# ai_breakout_apa102.net
KiCad netlist of a schematic drawn in EAGLE
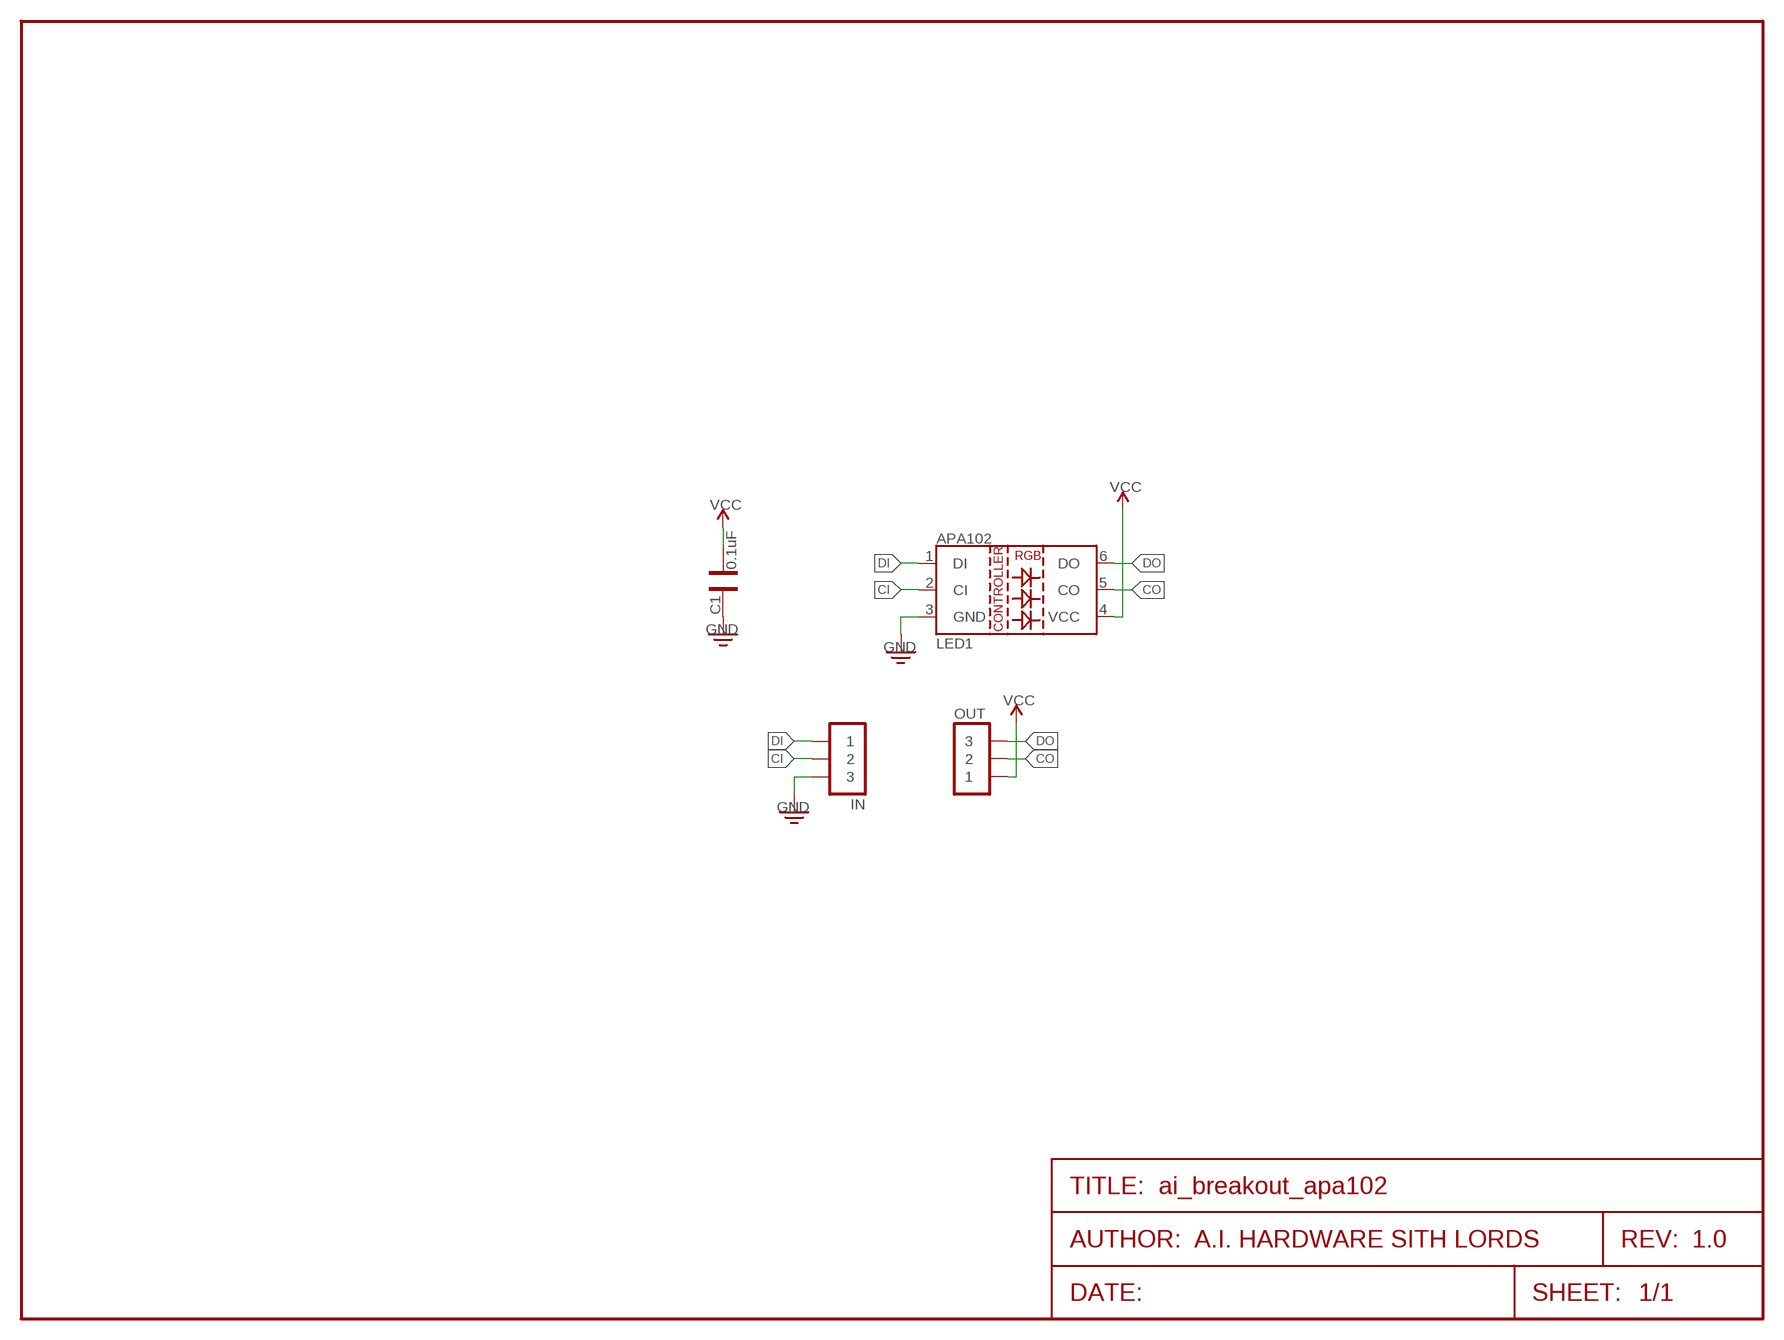
[diagram p0: schematic, sheet 1]

(export (version "E")
  (design (tool "Eeschema 10.0.6"))
  (components
    (comp (ref "C1")
      (value "0.1uF")
      (footprint "eagle-import:CAP-0402")
      (libsource (lib "eagle-import") (part "CAP0402"))
    )
    (comp (ref "IN")
      (value "1X03")
      (footprint "eagle-import:1X03")
      (libsource (lib "eagle-import") (part "1X03"))
    )
    (comp (ref "LED1")
      (value "LED-APA102")
      (footprint "eagle-import:LED-APA102")
      (libsource (lib "eagle-import") (part "LED-APA102"))
    )
    (comp (ref "OUT")
      (value "1X03NOFIRST")
      (footprint "eagle-import:1X03-NOFIRST")
      (libsource (lib "eagle-import") (part "1X03NOFIRST"))
    )
  )
  (nets
    (net (code "1") (name "CI") (class "Default")
      (node (ref "IN") (pin "2") (pinfunction "2_2") (pintype "bidirectional"))
      (node (ref "LED1") (pin "2") (pinfunction "CI_2") (pintype "bidirectional"))
    )
    (net (code "2") (name "CO") (class "Default")
      (node (ref "LED1") (pin "5") (pinfunction "CO_5") (pintype "bidirectional"))
      (node (ref "OUT") (pin "2") (pinfunction "2_2") (pintype "bidirectional"))
    )
    (net (code "3") (name "DI") (class "Default")
      (node (ref "IN") (pin "1") (pinfunction "1_1") (pintype "bidirectional"))
      (node (ref "LED1") (pin "1") (pinfunction "DI_1") (pintype "bidirectional"))
    )
    (net (code "4") (name "DO") (class "Default")
      (node (ref "LED1") (pin "6") (pinfunction "DO_6") (pintype "bidirectional"))
      (node (ref "OUT") (pin "3") (pinfunction "3_3") (pintype "bidirectional"))
    )
    (net (code "5") (name "GND") (class "Default")
      (node (ref "C1") (pin "2") (pinfunction "2_2") (pintype "passive"))
      (node (ref "IN") (pin "3") (pinfunction "3_3") (pintype "bidirectional"))
      (node (ref "LED1") (pin "3") (pinfunction "GND_3") (pintype "bidirectional"))
    )
    (net (code "6") (name "VCC") (class "Default")
      (node (ref "C1") (pin "1") (pinfunction "1_1") (pintype "passive"))
      (node (ref "LED1") (pin "4") (pinfunction "VCC_4") (pintype "bidirectional"))
      (node (ref "OUT") (pin "1") (pinfunction "1_1") (pintype "bidirectional"))
    )
  )
)
